# IR7.net
KiCad netlist of a schematic drawn in EAGLE
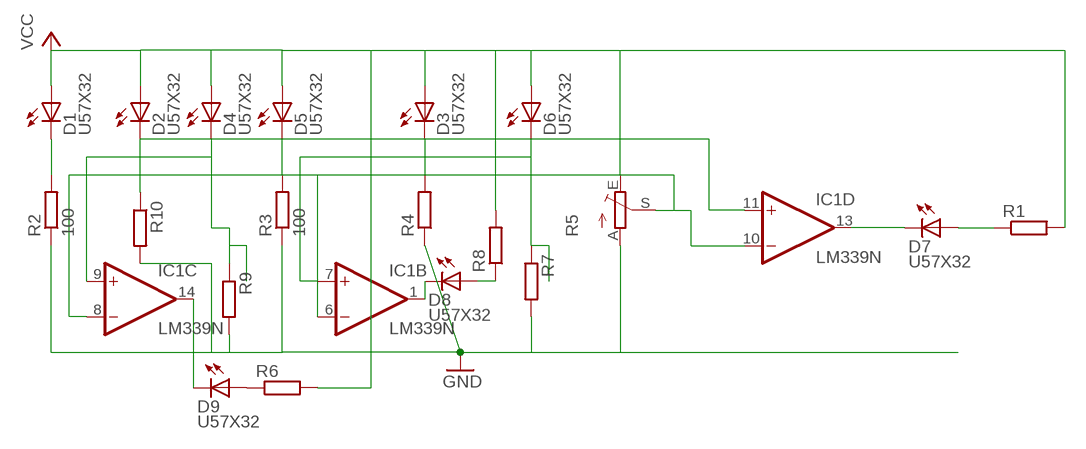
[diagram p0: schematic, sheet 1]

(export (version "E")
  (design (tool "Eeschema 10.0.6"))
  (components
    (comp (ref "D1")
      (value "U57X32")
      (footprint "eagle-import:U57X32")
      (libsource (lib "eagle-import") (part "U57X32"))
    )
    (comp (ref "D2")
      (value "U57X32")
      (footprint "eagle-import:U57X32")
      (libsource (lib "eagle-import") (part "U57X32"))
    )
    (comp (ref "D3")
      (value "U57X32")
      (footprint "eagle-import:U57X32")
      (libsource (lib "eagle-import") (part "U57X32"))
    )
    (comp (ref "D4")
      (value "U57X32")
      (footprint "eagle-import:U57X32")
      (libsource (lib "eagle-import") (part "U57X32"))
    )
    (comp (ref "D5")
      (value "U57X32")
      (footprint "eagle-import:U57X32")
      (libsource (lib "eagle-import") (part "U57X32"))
    )
    (comp (ref "D6")
      (value "U57X32")
      (footprint "eagle-import:U57X32")
      (libsource (lib "eagle-import") (part "U57X32"))
    )
    (comp (ref "D7")
      (value "U57X32")
      (footprint "eagle-import:U57X32")
      (libsource (lib "eagle-import") (part "U57X32"))
    )
    (comp (ref "D8")
      (value "U57X32")
      (footprint "eagle-import:U57X32")
      (libsource (lib "eagle-import") (part "U57X32"))
    )
    (comp (ref "D9")
      (value "U57X32")
      (footprint "eagle-import:U57X32")
      (libsource (lib "eagle-import") (part "U57X32"))
    )
    (comp (ref "IC1")
      (value "LM339N")
      (footprint "eagle-import:DIL14")
      (libsource (lib "eagle-import") (part "LM339N"))
    )
    (comp (ref "R1")
      (value "R-EU_0204/7")
      (footprint "eagle-import:0204_7")
      (libsource (lib "eagle-import") (part "R-EU_0204/7"))
    )
    (comp (ref "R2")
      (value "100")
      (footprint "eagle-import:0204_7")
      (libsource (lib "eagle-import") (part "R-EU_0204/7"))
    )
    (comp (ref "R3")
      (value "100")
      (footprint "eagle-import:0204_7")
      (libsource (lib "eagle-import") (part "R-EU_0204/7"))
    )
    (comp (ref "R4")
      (value "R-EU_0204/7")
      (footprint "eagle-import:0204_7")
      (libsource (lib "eagle-import") (part "R-EU_0204/7"))
    )
    (comp (ref "R5")
      (value "TRIM_1234-S64YW")
      (footprint "eagle-import:S64YW")
      (libsource (lib "eagle-import") (part "TRIM_1234-S64YW"))
    )
    (comp (ref "R6")
      (value "R-EU_0204/7")
      (footprint "eagle-import:0204_7")
      (libsource (lib "eagle-import") (part "R-EU_0204/7"))
    )
    (comp (ref "R7")
      (value "R-EU_0204/7")
      (footprint "eagle-import:0204_7")
      (libsource (lib "eagle-import") (part "R-EU_0204/7"))
    )
    (comp (ref "R8")
      (value "R-EU_0204/7")
      (footprint "eagle-import:0204_7")
      (libsource (lib "eagle-import") (part "R-EU_0204/7"))
    )
    (comp (ref "R9")
      (value "R-EU_0204/7")
      (footprint "eagle-import:0204_7")
      (libsource (lib "eagle-import") (part "R-EU_0204/7"))
    )
    (comp (ref "R10")
      (value "R-EU_0204/7")
      (footprint "eagle-import:0204_7")
      (libsource (lib "eagle-import") (part "R-EU_0204/7"))
    )
  )
  (nets
    (net (code "1") (name "GND") (class "Default")
      (node (ref "R10") (pin "2") (pinfunction "2_2") (pintype "passive"))
      (node (ref "R2") (pin "1") (pinfunction "1_1") (pintype "passive"))
      (node (ref "R3") (pin "1") (pinfunction "1_1") (pintype "passive"))
      (node (ref "R4") (pin "1") (pinfunction "1_1") (pintype "passive"))
      (node (ref "R5") (pin "A") (pinfunction "A_A") (pintype "passive"))
      (node (ref "R7") (pin "2") (pinfunction "2_2") (pintype "passive"))
      (node (ref "R9") (pin "2") (pinfunction "2_2") (pintype "passive"))
    )
    (net (code "2") (name "Net-(D1-C)") (class "Default")
      (node (ref "D1") (pin "K") (pinfunction "C_K") (pintype "passive"))
      (node (ref "R2") (pin "2") (pinfunction "2_2") (pintype "passive"))
    )
    (net (code "3") (name "Net-(D2-C)") (class "Default")
      (node (ref "D2") (pin "K") (pinfunction "C_K") (pintype "passive"))
      (node (ref "IC1") (pin "11") (pinfunction "+IN_11") (pintype "input"))
      (node (ref "R10") (pin "1") (pinfunction "1_1") (pintype "passive"))
    )
    (net (code "4") (name "Net-(D3-C)") (class "Default")
      (node (ref "D3") (pin "K") (pinfunction "C_K") (pintype "passive"))
      (node (ref "R4") (pin "2") (pinfunction "2_2") (pintype "passive"))
    )
    (net (code "5") (name "Net-(D4-C)") (class "Default")
      (node (ref "D4") (pin "K") (pinfunction "C_K") (pintype "passive"))
      (node (ref "IC1") (pin "9") (pinfunction "+IN_9") (pintype "input"))
      (node (ref "R9") (pin "1") (pinfunction "1_1") (pintype "passive"))
    )
    (net (code "6") (name "Net-(D5-C)") (class "Default")
      (node (ref "D5") (pin "K") (pinfunction "C_K") (pintype "passive"))
      (node (ref "R3") (pin "2") (pinfunction "2_2") (pintype "passive"))
    )
    (net (code "7") (name "Net-(D6-C)") (class "Default")
      (node (ref "D6") (pin "K") (pinfunction "C_K") (pintype "passive"))
      (node (ref "IC1") (pin "7") (pinfunction "+IN_7") (pintype "input"))
      (node (ref "R7") (pin "1") (pinfunction "1_1") (pintype "passive"))
    )
    (net (code "8") (name "Net-(D7-C)") (class "Default")
      (node (ref "D7") (pin "K") (pinfunction "C_K") (pintype "passive"))
      (node (ref "IC1") (pin "13") (pinfunction "OUT_13") (pintype "open_collector"))
    )
    (net (code "9") (name "Net-(D7-PadA)") (class "Default")
      (node (ref "D7") (pin "A") (pinfunction "A_A") (pintype "passive"))
      (node (ref "R1") (pin "1") (pinfunction "1_1") (pintype "passive"))
    )
    (net (code "10") (name "Net-(D8-C)") (class "Default")
      (node (ref "D8") (pin "K") (pinfunction "C_K") (pintype "passive"))
      (node (ref "IC1") (pin "1") (pinfunction "OUT_1") (pintype "open_collector"))
    )
    (net (code "11") (name "Net-(D8-PadA)") (class "Default")
      (node (ref "D8") (pin "A") (pinfunction "A_A") (pintype "passive"))
      (node (ref "R8") (pin "1") (pinfunction "1_1") (pintype "passive"))
    )
    (net (code "12") (name "Net-(D9-C)") (class "Default")
      (node (ref "D9") (pin "K") (pinfunction "C_K") (pintype "passive"))
      (node (ref "IC1") (pin "14") (pinfunction "OUT_14") (pintype "open_collector"))
    )
    (net (code "13") (name "Net-(D9-PadA)") (class "Default")
      (node (ref "D9") (pin "A") (pinfunction "A_A") (pintype "passive"))
      (node (ref "R6") (pin "1") (pinfunction "1_1") (pintype "passive"))
    )
    (net (code "14") (name "Net-(IC1B--IN)") (class "Default")
      (node (ref "IC1") (pin "10") (pinfunction "-IN_10") (pintype "input"))
      (node (ref "IC1") (pin "6") (pinfunction "-IN_6") (pintype "input"))
      (node (ref "IC1") (pin "8") (pinfunction "-IN_8") (pintype "input"))
      (node (ref "R5") (pin "S") (pinfunction "S_S") (pintype "passive"))
    )
    (net (code "15") (name "VCC") (class "Default")
      (node (ref "D1") (pin "A") (pinfunction "A_A") (pintype "passive"))
      (node (ref "D2") (pin "A") (pinfunction "A_A") (pintype "passive"))
      (node (ref "D3") (pin "A") (pinfunction "A_A") (pintype "passive"))
      (node (ref "D4") (pin "A") (pinfunction "A_A") (pintype "passive"))
      (node (ref "D5") (pin "A") (pinfunction "A_A") (pintype "passive"))
      (node (ref "D6") (pin "A") (pinfunction "A_A") (pintype "passive"))
      (node (ref "R1") (pin "2") (pinfunction "2_2") (pintype "passive"))
      (node (ref "R5") (pin "E") (pinfunction "E_E") (pintype "passive"))
      (node (ref "R6") (pin "2") (pinfunction "2_2") (pintype "passive"))
      (node (ref "R8") (pin "2") (pinfunction "2_2") (pintype "passive"))
    )
    (net (code "16") (name "unconnected-(R5-S-PadS@1)") (class "Default")
      (node (ref "R5") (pin "S@1") (pinfunction "S_S@1") (pintype "passive"))
    )
  )
)
